# SCH_Dual_Power_Supply_2023-09-18.net
KiCad netlist of a schematic drawn in EasyEDA
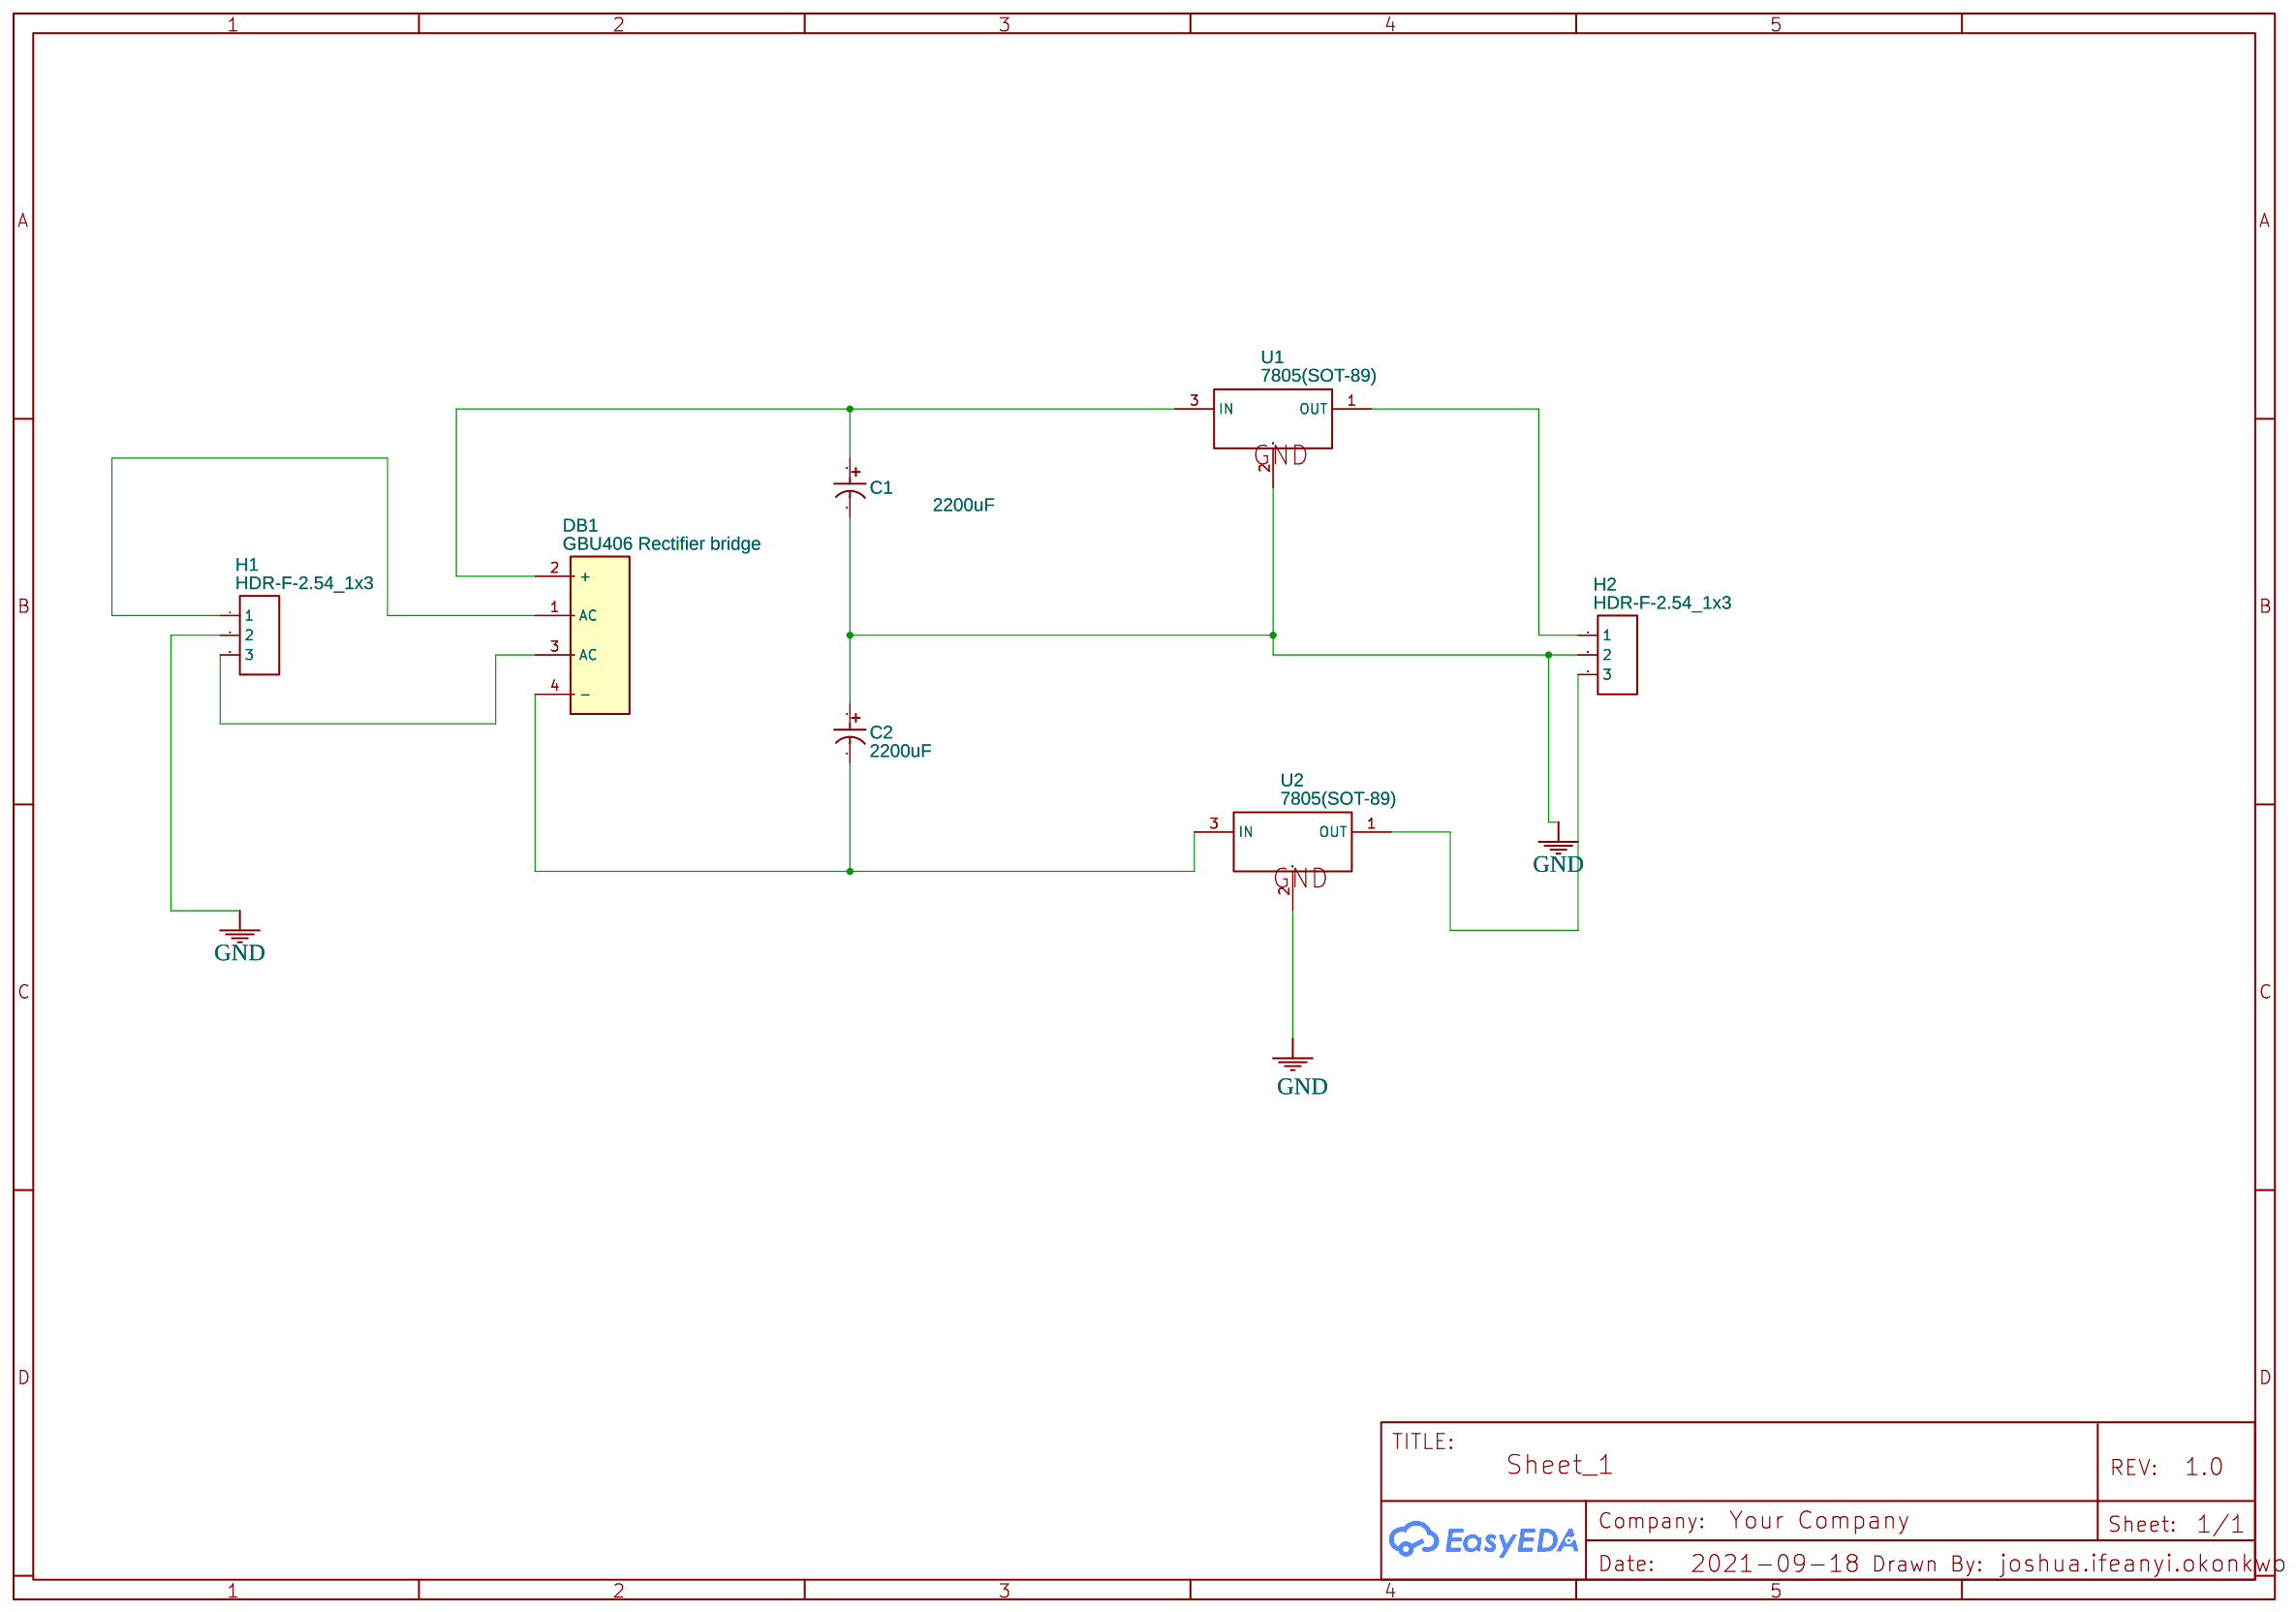
[diagram p0: schematic sheet]

(export (version "E")
  (design (tool "Eeschema 10.0.6"))
  (components
    (comp (ref "C1")
      (value "2200uF")
      (fields
        (field (name "Manufacturer Part") "KM228M025J20RR0VH2FP0")
        (field (name "Manufacturer") "CX(承兴)")
      )
      (libsource (lib "") (part "2200uF 25V 13*20"))
    )
    (comp (ref "C2")
      (value "2200uF")
      (fields
        (field (name "Manufacturer Part") "KM228M025J20RR0VH2FP0")
        (field (name "Manufacturer") "CX(承兴)")
      )
      (libsource (lib "") (part "2200uF 25V 13*20"))
    )
    (comp (ref "DB1")
      (value "GBU406 Rectifier bridge")
      (fields (field (name "Manufacturer Part") "GBU406") (field (name "Manufacturer") "MDD"))
      (libsource (lib "") (part "GBU406 Rectifier bridge"))
    )
    (comp (ref "H1") (value "HDR-F-2.54_1x3") (libsource (lib "") (part "HDR-F-2.54_1x3")))
    (comp (ref "H2") (value "HDR-F-2.54_1x3") (libsource (lib "") (part "HDR-F-2.54_1x3")))
    (comp (ref "U1")
      (value "7805(SOT-89)")
      (fields (field (name "Manufacturer Part") "CJ78L05") (field (name "Manufacturer") "CJ"))
      (libsource (lib "") (part "7805(SOT-89)"))
    )
    (comp (ref "U2")
      (value "7805(SOT-89)")
      (fields (field (name "Manufacturer Part") "CJ78L05") (field (name "Manufacturer") "CJ"))
      (libsource (lib "") (part "7805(SOT-89)"))
    )
  )
  (nets
    (net (code "1") (name "GND") (class "Default")
      (node (ref "C1") (pin "2") (pinfunction "2_2") (pintype "input"))
      (node (ref "C2") (pin "1") (pinfunction "1_1") (pintype "input"))
      (node (ref "H1") (pin "2") (pinfunction "2_2") (pintype "input"))
      (node (ref "H2") (pin "2") (pinfunction "2_2") (pintype "input"))
      (node (ref "U1") (pin "2") (pinfunction "GND_2") (pintype "passive"))
      (node (ref "U2") (pin "2") (pinfunction "GND_2") (pintype "passive"))
    )
    (net (code "2") (name "Net-(DB1-+)") (class "Default")
      (node (ref "C1") (pin "1") (pinfunction "1_1") (pintype "input"))
      (node (ref "DB1") (pin "2") (pinfunction "+_2") (pintype "input"))
      (node (ref "U1") (pin "3") (pinfunction "IN_3") (pintype "passive"))
    )
    (net (code "3") (name "Net-(DB1--)") (class "Default")
      (node (ref "C2") (pin "2") (pinfunction "2_2") (pintype "input"))
      (node (ref "DB1") (pin "4") (pinfunction "-_4") (pintype "input"))
      (node (ref "U2") (pin "3") (pinfunction "IN_3") (pintype "passive"))
    )
    (net (code "4") (name "Net-(DB1-AC-Pad1)") (class "Default")
      (node (ref "DB1") (pin "1") (pinfunction "AC_1") (pintype "input"))
      (node (ref "H1") (pin "1") (pinfunction "1_1") (pintype "input"))
    )
    (net (code "5") (name "Net-(DB1-AC-Pad3)") (class "Default")
      (node (ref "DB1") (pin "3") (pinfunction "AC_3") (pintype "input"))
      (node (ref "H1") (pin "3") (pinfunction "3_3") (pintype "input"))
    )
    (net (code "6") (name "Net-(U1-OUT)") (class "Default")
      (node (ref "H2") (pin "1") (pinfunction "1_1") (pintype "input"))
      (node (ref "U1") (pin "1") (pinfunction "OUT_1") (pintype "passive"))
    )
    (net (code "7") (name "Net-(U2-OUT)") (class "Default")
      (node (ref "H2") (pin "3") (pinfunction "3_3") (pintype "input"))
      (node (ref "U2") (pin "1") (pinfunction "OUT_1") (pintype "passive"))
    )
  )
)
